# IO_Ports.net
KiCad netlist of a schematic drawn in Altium Designer
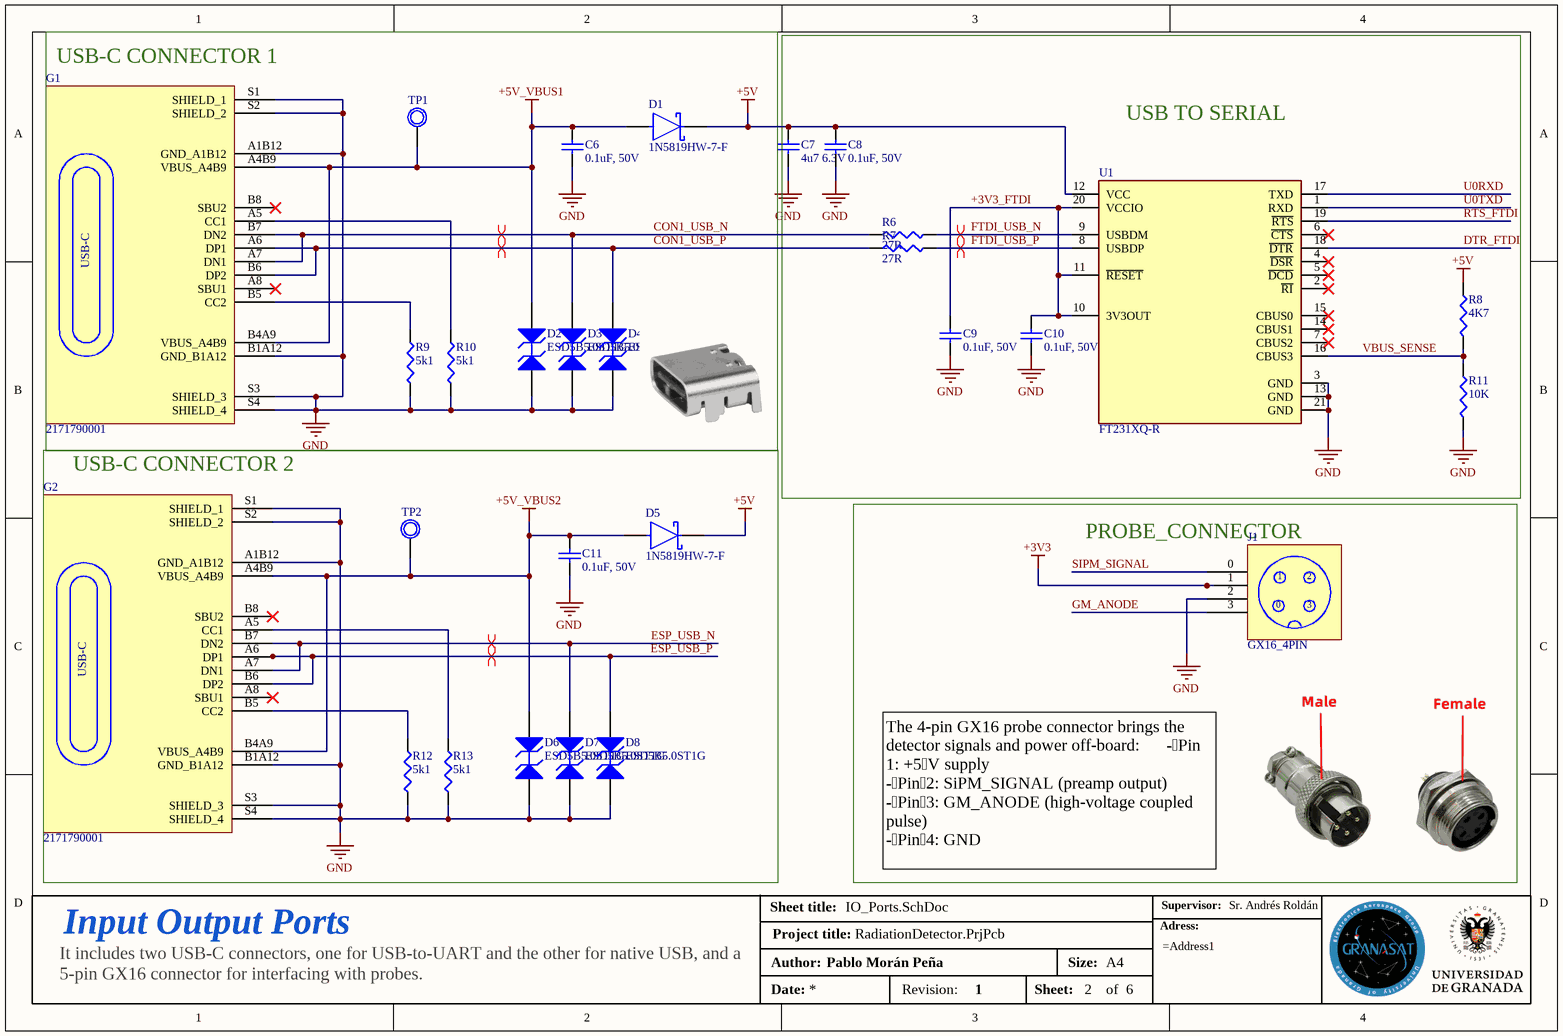
[diagram p0: IO_Ports.SchDoc]

(export (version "E")
  (design (tool "Eeschema 10.0.6"))
  (components
    (comp (ref "C6")
      (value "0.1uF, 50V")
      (footprint "CAP 0402_1005")
      (description "CAP CER 0.1UF 50V X7R 0402")
      (fields
        (field (name "MANUFACTURER") "Samsung")
        (field (name "MANUFACTURER PART NUMBER") "CL05B104KB5NNNC")
      )
      (libsource (lib "Schlib") (part "CL05B104KB5NNNC"))
    )
    (comp (ref "C7")
      (value "4u7 6.3V")
      (footprint "CAP 0402_1005")
      (description "CAP CER 4.7UF 6.3V X5R 0402")
      (fields
        (field (name "MANUFACTURER") "Samsung")
        (field (name "MANUFACTURER PART NUMBER") "CL05A475KQ5NRNC")
      )
      (libsource (lib "Schlib") (part "CL05A475KQ5NRNC"))
    )
    (comp (ref "C8")
      (value "0.1uF, 50V")
      (footprint "CAP 0402_1005")
      (description "CAP CER 0.1UF 50V X7R 0402")
      (fields
        (field (name "MANUFACTURER") "Samsung")
        (field (name "MANUFACTURER PART NUMBER") "CL05B104KB5NNNC")
      )
      (libsource (lib "Schlib") (part "CL05B104KB5NNNC"))
    )
    (comp (ref "C9")
      (value "0.1uF, 50V")
      (footprint "CAP 0402_1005")
      (description "CAP CER 0.1UF 50V X7R 0402")
      (fields
        (field (name "MANUFACTURER") "Samsung")
        (field (name "MANUFACTURER PART NUMBER") "CL05B104KB5NNNC")
      )
      (libsource (lib "Schlib") (part "CL05B104KB5NNNC"))
    )
    (comp (ref "C10")
      (value "0.1uF, 50V")
      (footprint "CAP 0402_1005")
      (description "CAP CER 0.1UF 50V X7R 0402")
      (fields
        (field (name "MANUFACTURER") "Samsung")
        (field (name "MANUFACTURER PART NUMBER") "CL05B104KB5NNNC")
      )
      (libsource (lib "Schlib") (part "CL05B104KB5NNNC"))
    )
    (comp (ref "C11")
      (value "0.1uF, 50V")
      (footprint "CAP 0402_1005")
      (description "CAP CER 0.1UF 50V X7R 0402")
      (fields
        (field (name "MANUFACTURER") "Samsung")
        (field (name "MANUFACTURER PART NUMBER") "CL05B104KB5NNNC")
      )
      (libsource (lib "Schlib") (part "CL05B104KB5NNNC"))
    )
    (comp (ref "D1")
      (value "1N5819HW-7-F")
      (footprint "FP-SOD123-MFG")
      (description "DIODE SCHOTTKY 40V 1A SOD123")
      (fields (field (name "MANUFACTURER") "Diodes") (field (name "LCSC PART NUMBER") "C82544"))
      (libsource (lib "Schlib") (part "1N5819HW-7-F"))
    )
    (comp (ref "D2")
      (value "ESD5B5.0ST1G")
      (footprint "ONSC-SOD-523-2-502-01_C_V")
      (description "TVS DIODE 5VWM SOD523")
      (fields (field (name "MANUFACTURER") "ON Semiconductor") (field (name "LCSC PART NUMBER") "C93623"))
      (libsource (lib "Schlib") (part "ESD5B5.0ST1G"))
    )
    (comp (ref "D3")
      (value "ESD5B5.0ST1G")
      (footprint "ONSC-SOD-523-2-502-01_C_V")
      (description "TVS DIODE 5VWM SOD523")
      (fields (field (name "MANUFACTURER") "ON Semiconductor") (field (name "LCSC PART NUMBER") "C93623"))
      (libsource (lib "Schlib") (part "ESD5B5.0ST1G"))
    )
    (comp (ref "D4")
      (value "ESD5B5.0ST1G")
      (footprint "ONSC-SOD-523-2-502-01_C_V")
      (description "TVS DIODE 5VWM SOD523")
      (fields (field (name "MANUFACTURER") "ON Semiconductor") (field (name "LCSC PART NUMBER") "C93623"))
      (libsource (lib "Schlib") (part "ESD5B5.0ST1G"))
    )
    (comp (ref "D5")
      (value "1N5819HW-7-F")
      (footprint "FP-SOD123-MFG")
      (description "DIODE SCHOTTKY 40V 1A SOD123")
      (fields (field (name "MANUFACTURER") "Diodes") (field (name "LCSC PART NUMBER") "C82544"))
      (libsource (lib "Schlib") (part "1N5819HW-7-F"))
    )
    (comp (ref "D6")
      (value "ESD5B5.0ST1G")
      (footprint "ONSC-SOD-523-2-502-01_C_V")
      (description "TVS DIODE 5VWM SOD523")
      (fields (field (name "MANUFACTURER") "ON Semiconductor") (field (name "LCSC PART NUMBER") "C93623"))
      (libsource (lib "Schlib") (part "ESD5B5.0ST1G"))
    )
    (comp (ref "D7")
      (value "ESD5B5.0ST1G")
      (footprint "ONSC-SOD-523-2-502-01_C_V")
      (description "TVS DIODE 5VWM SOD523")
      (fields (field (name "MANUFACTURER") "ON Semiconductor") (field (name "LCSC PART NUMBER") "C93623"))
      (libsource (lib "Schlib") (part "ESD5B5.0ST1G"))
    )
    (comp (ref "D8")
      (value "ESD5B5.0ST1G")
      (footprint "ONSC-SOD-523-2-502-01_C_V")
      (description "TVS DIODE 5VWM SOD523")
      (fields (field (name "MANUFACTURER") "ON Semiconductor") (field (name "LCSC PART NUMBER") "C93623"))
      (libsource (lib "Schlib") (part "ESD5B5.0ST1G"))
    )
    (comp (ref "G1")
      (value "2171790001")
      (footprint "FP-2171790001-MFG")
      (description "CONN RCP USB2.0 TYP C 24P SMD RA")
      (fields (field (name "MANUFACTURER") "Molex") (field (name "MANUFACTURER PART NUMBER") "217179-0001"))
      (libsource (lib "Schlib") (part "217179-0001"))
    )
    (comp (ref "G2")
      (value "2171790001")
      (footprint "FP-2171790001-MFG")
      (description "CONN RCP USB2.0 TYP C 24P SMD RA")
      (fields (field (name "MANUFACTURER") "Molex") (field (name "MANUFACTURER PART NUMBER") "217179-0001"))
      (libsource (lib "Schlib") (part "217179-0001"))
    )
    (comp (ref "J1")
      (value "GX16_4PIN")
      (footprint "WIRE_HARNESS_4PIN_HV")
      (libsource (lib "Schlib") (part "GX16_4PIN"))
    )
    (comp (ref "R6")
      (value "27R")
      (footprint "RESC1005X37N")
      (description "RES SMD 27 OHM 1% 1/16W 0402")
      (fields
        (field (name "MANUFACTURER") "Yageo")
        (field (name "MANUFACTURER PART NUMBER") "AC0402FR-0727RL")
      )
      (libsource (lib "Schlib") (part "AC0402FR-0727RL"))
    )
    (comp (ref "R7")
      (value "27R")
      (footprint "RESC1005X37N")
      (description "RES SMD 27 OHM 1% 1/16W 0402")
      (fields
        (field (name "MANUFACTURER") "Yageo")
        (field (name "MANUFACTURER PART NUMBER") "AC0402FR-0727RL")
      )
      (libsource (lib "Schlib") (part "AC0402FR-0727RL"))
    )
    (comp (ref "R8")
      (value "4K7")
      (footprint "RESC1005X37N")
      (description "RES SMD 4.7K OHM 1% 1/16W 0402")
      (fields
        (field (name "MANUFACTURER") "Yageo")
        (field (name "MANUFACTURER PART NUMBER") "AC0402FR-074K7L")
      )
      (libsource (lib "Schlib") (part "AC0402FR-074K7L"))
    )
    (comp (ref "R9")
      (value "5k1")
      (footprint "RESC1005X37N")
      (description "RES SMD 5.1K OHM 1% 1/16W 0402")
      (fields
        (field (name "MANUFACTURER") "Yageo")
        (field (name "MANUFACTURER PART NUMBER") "AC0402FR-075K1L")
      )
      (libsource (lib "Schlib") (part "AC0402FR-075K1L"))
    )
    (comp (ref "R10")
      (value "5k1")
      (footprint "RESC1005X37N")
      (description "RES SMD 5.1K OHM 1% 1/16W 0402")
      (fields
        (field (name "MANUFACTURER") "Yageo")
        (field (name "MANUFACTURER PART NUMBER") "AC0402FR-075K1L")
      )
      (libsource (lib "Schlib") (part "AC0402FR-075K1L"))
    )
    (comp (ref "R11")
      (value "10K")
      (footprint "RESC1005X37N")
      (description "RES SMD 10K OHM 1% 1/16W 0402")
      (fields
        (field (name "MANUFACTURER") "Yageo")
        (field (name "MANUFACTURER PART NUMBER") "AC0402FR-0710KL")
      )
      (libsource (lib "Schlib") (part "AC0402FR-0710KL"))
    )
    (comp (ref "R12")
      (value "5k1")
      (footprint "RESC1005X37N")
      (description "RES SMD 5.1K OHM 1% 1/16W 0402")
      (fields
        (field (name "MANUFACTURER") "Yageo")
        (field (name "MANUFACTURER PART NUMBER") "AC0402FR-075K1L")
      )
      (libsource (lib "Schlib") (part "AC0402FR-075K1L"))
    )
    (comp (ref "R13")
      (value "5k1")
      (footprint "RESC1005X37N")
      (description "RES SMD 5.1K OHM 1% 1/16W 0402")
      (fields
        (field (name "MANUFACTURER") "Yageo")
        (field (name "MANUFACTURER PART NUMBER") "AC0402FR-075K1L")
      )
      (libsource (lib "Schlib") (part "AC0402FR-075K1L"))
    )
    (comp (ref "TP1")
      (value "Testpoint")
      (footprint "Testpoint")
      (libsource (lib "Schlib") (part "Testpoint"))
    )
    (comp (ref "TP2")
      (value "Testpoint")
      (footprint "Testpoint")
      (libsource (lib "Schlib") (part "Testpoint"))
    )
    (comp (ref "U1")
      (value "FT231XQ-R")
      (footprint "FP-QFN-20-MFG")
      (description "IC USB SERIAL FULL UART 20QFN")
      (fields (field (name "MANUFACTURER") "FTDI") (field (name "LCSC PART NUMBER") "C132159"))
      (libsource (lib "Schlib") (part "FT231XQ-R"))
    )
  )
  (nets
    (net (code "1") (name "+3V3") (class "Default")
      (node (ref "J1") (pin "1") (pinfunction "1_1") (pintype "passive"))
    )
    (net (code "2") (name "+5V") (class "Default")
      (node (ref "C7") (pin "2") (pinfunction "2_2") (pintype "passive"))
      (node (ref "C8") (pin "2") (pinfunction "2_2") (pintype "passive"))
      (node (ref "D1") (pin "1") (pinfunction "C_1") (pintype "passive"))
      (node (ref "D5") (pin "1") (pinfunction "C_1") (pintype "passive"))
      (node (ref "R8") (pin "2") (pinfunction "2_2") (pintype "passive"))
      (node (ref "U1") (pin "12") (pinfunction "VCC_12") (pintype "passive"))
    )
    (net (code "3") (name "+5V_VBUS1") (class "Default")
      (node (ref "C6") (pin "2") (pinfunction "2_2") (pintype "passive"))
      (node (ref "D1") (pin "2") (pinfunction "A_2") (pintype "passive"))
      (node (ref "D2") (pin "2") (pinfunction "A2_2") (pintype "passive"))
      (node (ref "G1") (pin "A4B9") (pinfunction "VBUS_A4B9_A4B9") (pintype "passive"))
      (node (ref "G1") (pin "B4A9") (pinfunction "VBUS_A4B9_B4A9") (pintype "passive"))
      (node (ref "TP1") (pin "1") (pinfunction "1_1") (pintype "passive"))
    )
    (net (code "4") (name "+5V_VBUS2") (class "Default")
      (node (ref "C11") (pin "2") (pinfunction "2_2") (pintype "passive"))
      (node (ref "D5") (pin "2") (pinfunction "A_2") (pintype "passive"))
      (node (ref "D6") (pin "2") (pinfunction "A2_2") (pintype "passive"))
      (node (ref "G2") (pin "A4B9") (pinfunction "VBUS_A4B9_A4B9") (pintype "passive"))
      (node (ref "G2") (pin "B4A9") (pinfunction "VBUS_A4B9_B4A9") (pintype "passive"))
      (node (ref "TP2") (pin "1") (pinfunction "1_1") (pintype "passive"))
    )
    (net (code "5") (name "/+3V3_FTDI") (class "Default")
      (node (ref "C10") (pin "2") (pinfunction "2_2") (pintype "passive"))
      (node (ref "C9") (pin "2") (pinfunction "2_2") (pintype "passive"))
      (node (ref "U1") (pin "10") (pinfunction "3V3OUT_10") (pintype "passive"))
      (node (ref "U1") (pin "11") (pinfunction "~{RESET}_11") (pintype "passive"))
      (node (ref "U1") (pin "20") (pinfunction "VCCIO_20") (pintype "passive"))
    )
    (net (code "6") (name "/CON1_USB_N") (class "Default")
      (node (ref "D3") (pin "2") (pinfunction "A2_2") (pintype "passive"))
      (node (ref "G1") (pin "A7") (pinfunction "DN1_A7") (pintype "passive"))
      (node (ref "G1") (pin "B7") (pinfunction "DN2_B7") (pintype "passive"))
      (node (ref "R6") (pin "1") (pinfunction "1_1") (pintype "passive"))
    )
    (net (code "7") (name "/CON1_USB_P") (class "Default")
      (node (ref "D4") (pin "2") (pinfunction "A2_2") (pintype "passive"))
      (node (ref "G1") (pin "A6") (pinfunction "DP1_A6") (pintype "passive"))
      (node (ref "G1") (pin "B6") (pinfunction "DP2_B6") (pintype "passive"))
      (node (ref "R7") (pin "1") (pinfunction "1_1") (pintype "passive"))
    )
    (net (code "8") (name "/DTR_FTDI") (class "Default")
      (node (ref "U1") (pin "18") (pinfunction "~{DTR}_18") (pintype "passive"))
    )
    (net (code "9") (name "/ESP_USB_N") (class "Default")
      (node (ref "D7") (pin "2") (pinfunction "A2_2") (pintype "passive"))
      (node (ref "G2") (pin "A7") (pinfunction "DN1_A7") (pintype "passive"))
      (node (ref "G2") (pin "B7") (pinfunction "DN2_B7") (pintype "passive"))
    )
    (net (code "10") (name "/ESP_USB_P") (class "Default")
      (node (ref "D8") (pin "2") (pinfunction "A2_2") (pintype "passive"))
      (node (ref "G2") (pin "A6") (pinfunction "DP1_A6") (pintype "passive"))
      (node (ref "G2") (pin "B6") (pinfunction "DP2_B6") (pintype "passive"))
    )
    (net (code "11") (name "/FTDI_USB_N") (class "Default")
      (node (ref "R6") (pin "2") (pinfunction "2_2") (pintype "passive"))
      (node (ref "U1") (pin "9") (pinfunction "USBDM_9") (pintype "passive"))
    )
    (net (code "12") (name "/FTDI_USB_P") (class "Default")
      (node (ref "R7") (pin "2") (pinfunction "2_2") (pintype "passive"))
      (node (ref "U1") (pin "8") (pinfunction "USBDP_8") (pintype "passive"))
    )
    (net (code "13") (name "/GM_ANODE") (class "Default")
      (node (ref "J1") (pin "3") (pinfunction "3_3") (pintype "passive"))
    )
    (net (code "14") (name "/RTS_FTDI") (class "Default")
      (node (ref "U1") (pin "19") (pinfunction "~{RTS}_19") (pintype "passive"))
    )
    (net (code "15") (name "/SIPM_SIGNAL") (class "Default")
      (node (ref "J1") (pin "0") (pinfunction "0_0") (pintype "passive"))
    )
    (net (code "16") (name "/U0RXD") (class "Default")
      (node (ref "U1") (pin "17") (pinfunction "TXD_17") (pintype "passive"))
    )
    (net (code "17") (name "/U0TXD") (class "Default")
      (node (ref "U1") (pin "1") (pinfunction "RXD_1") (pintype "passive"))
    )
    (net (code "18") (name "/VBUS_SENSE") (class "Default")
      (node (ref "R11") (pin "2") (pinfunction "2_2") (pintype "passive"))
      (node (ref "R8") (pin "1") (pinfunction "1_1") (pintype "passive"))
      (node (ref "U1") (pin "16") (pinfunction "CBUS3_16") (pintype "passive"))
    )
    (net (code "19") (name "GND") (class "Default")
      (node (ref "C10") (pin "1") (pinfunction "1_1") (pintype "passive"))
      (node (ref "C11") (pin "1") (pinfunction "1_1") (pintype "passive"))
      (node (ref "C6") (pin "1") (pinfunction "1_1") (pintype "passive"))
      (node (ref "C7") (pin "1") (pinfunction "1_1") (pintype "passive"))
      (node (ref "C8") (pin "1") (pinfunction "1_1") (pintype "passive"))
      (node (ref "C9") (pin "1") (pinfunction "1_1") (pintype "passive"))
      (node (ref "D2") (pin "1") (pinfunction "A1_1") (pintype "passive"))
      (node (ref "D3") (pin "1") (pinfunction "A1_1") (pintype "passive"))
      (node (ref "D4") (pin "1") (pinfunction "A1_1") (pintype "passive"))
      (node (ref "D6") (pin "1") (pinfunction "A1_1") (pintype "passive"))
      (node (ref "D7") (pin "1") (pinfunction "A1_1") (pintype "passive"))
      (node (ref "D8") (pin "1") (pinfunction "A1_1") (pintype "passive"))
      (node (ref "G1") (pin "A1B12") (pinfunction "GND_A1B12_A1B12") (pintype "passive"))
      (node (ref "G1") (pin "B1A12") (pinfunction "GND_B1A12_B1A12") (pintype "passive"))
      (node (ref "G1") (pin "S1") (pinfunction "SHIELD_1_S1") (pintype "passive"))
      (node (ref "G1") (pin "S2") (pinfunction "SHIELD_2_S2") (pintype "passive"))
      (node (ref "G1") (pin "S3") (pinfunction "SHIELD_3_S3") (pintype "passive"))
      (node (ref "G1") (pin "S4") (pinfunction "SHIELD_4_S4") (pintype "passive"))
      (node (ref "G2") (pin "A1B12") (pinfunction "GND_A1B12_A1B12") (pintype "passive"))
      (node (ref "G2") (pin "B1A12") (pinfunction "GND_B1A12_B1A12") (pintype "passive"))
      (node (ref "G2") (pin "S1") (pinfunction "SHIELD_1_S1") (pintype "passive"))
      (node (ref "G2") (pin "S2") (pinfunction "SHIELD_2_S2") (pintype "passive"))
      (node (ref "G2") (pin "S3") (pinfunction "SHIELD_3_S3") (pintype "passive"))
      (node (ref "G2") (pin "S4") (pinfunction "SHIELD_4_S4") (pintype "passive"))
      (node (ref "J1") (pin "2") (pinfunction "2_2") (pintype "passive"))
      (node (ref "R10") (pin "1") (pinfunction "1_1") (pintype "passive"))
      (node (ref "R11") (pin "1") (pinfunction "1_1") (pintype "passive"))
      (node (ref "R12") (pin "1") (pinfunction "1_1") (pintype "passive"))
      (node (ref "R13") (pin "1") (pinfunction "1_1") (pintype "passive"))
      (node (ref "R9") (pin "1") (pinfunction "1_1") (pintype "passive"))
      (node (ref "U1") (pin "13") (pinfunction "GND_13") (pintype "passive"))
      (node (ref "U1") (pin "21") (pinfunction "GND_21") (pintype "passive"))
      (node (ref "U1") (pin "3") (pinfunction "GND_3") (pintype "passive"))
    )
    (net (code "20") (name "Net-(G1-CC1)") (class "Default")
      (node (ref "G1") (pin "A5") (pinfunction "CC1_A5") (pintype "passive"))
      (node (ref "R10") (pin "2") (pinfunction "2_2") (pintype "passive"))
    )
    (net (code "21") (name "Net-(G1-CC2)") (class "Default")
      (node (ref "G1") (pin "B5") (pinfunction "CC2_B5") (pintype "passive"))
      (node (ref "R9") (pin "2") (pinfunction "2_2") (pintype "passive"))
    )
    (net (code "22") (name "Net-(G2-CC1)") (class "Default")
      (node (ref "G2") (pin "A5") (pinfunction "CC1_A5") (pintype "passive"))
      (node (ref "R13") (pin "2") (pinfunction "2_2") (pintype "passive"))
    )
    (net (code "23") (name "Net-(G2-CC2)") (class "Default")
      (node (ref "G2") (pin "B5") (pinfunction "CC2_B5") (pintype "passive"))
      (node (ref "R12") (pin "2") (pinfunction "2_2") (pintype "passive"))
    )
    (net (code "24") (name "unconnected-(G1-SBU1-PadA8)") (class "Default")
      (node (ref "G1") (pin "A8") (pinfunction "SBU1_A8") (pintype "passive+no_connect"))
    )
    (net (code "25") (name "unconnected-(G1-SBU2-PadB8)") (class "Default")
      (node (ref "G1") (pin "B8") (pinfunction "SBU2_B8") (pintype "passive+no_connect"))
    )
    (net (code "26") (name "unconnected-(G2-SBU1-PadA8)") (class "Default")
      (node (ref "G2") (pin "A8") (pinfunction "SBU1_A8") (pintype "passive+no_connect"))
    )
    (net (code "27") (name "unconnected-(G2-SBU2-PadB8)") (class "Default")
      (node (ref "G2") (pin "B8") (pinfunction "SBU2_B8") (pintype "passive+no_connect"))
    )
    (net (code "28") (name "unconnected-(U1-CBUS0-Pad15)") (class "Default")
      (node (ref "U1") (pin "15") (pinfunction "CBUS0_15") (pintype "passive+no_connect"))
    )
    (net (code "29") (name "unconnected-(U1-CBUS1-Pad14)") (class "Default")
      (node (ref "U1") (pin "14") (pinfunction "CBUS1_14") (pintype "passive+no_connect"))
    )
    (net (code "30") (name "unconnected-(U1-CBUS2-Pad7)") (class "Default")
      (node (ref "U1") (pin "7") (pinfunction "CBUS2_7") (pintype "passive+no_connect"))
    )
    (net (code "31") (name "unconnected-(U1-~{CTS}-Pad6)") (class "Default")
      (node (ref "U1") (pin "6") (pinfunction "~{CTS}_6") (pintype "passive+no_connect"))
    )
    (net (code "32") (name "unconnected-(U1-~{DCD}-Pad5)") (class "Default")
      (node (ref "U1") (pin "5") (pinfunction "~{DCD}_5") (pintype "passive+no_connect"))
    )
    (net (code "33") (name "unconnected-(U1-~{DSR}-Pad4)") (class "Default")
      (node (ref "U1") (pin "4") (pinfunction "~{DSR}_4") (pintype "passive+no_connect"))
    )
    (net (code "34") (name "unconnected-(U1-~{RI}-Pad2)") (class "Default")
      (node (ref "U1") (pin "2") (pinfunction "~{RI}_2") (pintype "passive+no_connect"))
    )
  )
)
